# ir-reciever-test.net
KiCad netlist of a schematic drawn in EAGLE
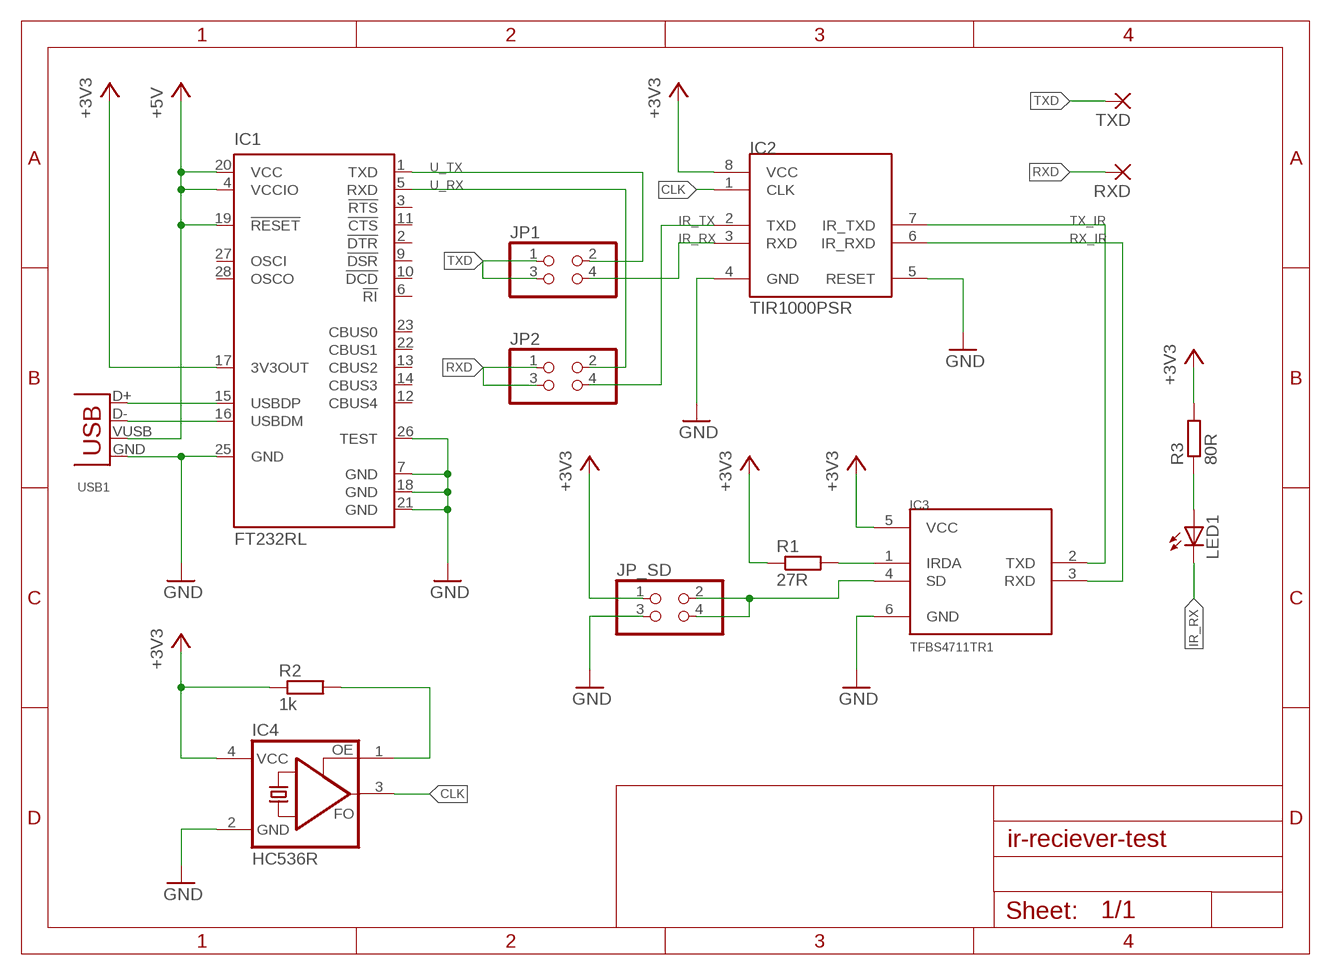
[diagram p0: schematic, sheet 1]

(export (version "E")
  (design (tool "Eeschema 10.0.6"))
  (components
    (comp (ref "IC1")
      (value "FT232RL")
      (footprint "eagle-import:SSOP28")
      (libsource (lib "eagle-import") (part "FT232RL"))
    )
    (comp (ref "IC2")
      (value "TIR1000PSR")
      (footprint "eagle-import:SO-08")
      (libsource (lib "eagle-import") (part "TIR1000PSR"))
    )
    (comp (ref "IC3")
      (value "TFBS4711TR1")
      (footprint "eagle-import:TFBS4711")
      (libsource (lib "eagle-import") (part "TFBS4711TR1"))
    )
    (comp (ref "IC4")
      (value "HC536R")
      (footprint "eagle-import:HC536")
      (libsource (lib "eagle-import") (part "HC536R"))
    )
    (comp (ref "JP1")
      (value "PINHD-2X02_2.54-SMD")
      (footprint "eagle-import:2X02SMD")
      (libsource (lib "eagle-import") (part "PINHD-2X02_2.54-SMD"))
    )
    (comp (ref "JP2")
      (value "PINHD-2X02_2.54-SMD")
      (footprint "eagle-import:2X02SMD")
      (libsource (lib "eagle-import") (part "PINHD-2X02_2.54-SMD"))
    )
    (comp (ref "JP_SD")
      (value "PINHD-2X02_2.54-SMD")
      (footprint "eagle-import:2X02SMD")
      (libsource (lib "eagle-import") (part "PINHD-2X02_2.54-SMD"))
    )
    (comp (ref "LED1")
      (value "LED3MM")
      (footprint "eagle-import:LED3MM")
      (libsource (lib "eagle-import") (part "LED3MM"))
    )
    (comp (ref "R1")
      (value "27R")
      (footprint "eagle-import:R1206")
      (libsource (lib "eagle-import") (part "R-EU_R1206"))
    )
    (comp (ref "R2")
      (value "1k")
      (footprint "eagle-import:R1206")
      (libsource (lib "eagle-import") (part "R-EU_R1206"))
    )
    (comp (ref "R3")
      (value "80R")
      (footprint "eagle-import:R1206")
      (libsource (lib "eagle-import") (part "R-EU_R1206"))
    )
    (comp (ref "RXD")
      (value "SMD5")
      (footprint "eagle-import:SMD2,54-5,08")
      (libsource (lib "eagle-import") (part "SMD5"))
    )
    (comp (ref "TXD")
      (value "SMD5")
      (footprint "eagle-import:SMD2,54-5,08")
      (libsource (lib "eagle-import") (part "SMD5"))
    )
    (comp (ref "USB1")
      (value "USB-B-S")
      (footprint "eagle-import:USB-B-SMT")
      (libsource (lib "eagle-import") (part "USB-B-S"))
    )
  )
  (nets
    (net (code "1") (name "+3V3") (class "Default")
      (node (ref "IC1") (pin "17") (pinfunction "3V3OUT_17") (pintype "output"))
      (node (ref "IC2") (pin "8") (pinfunction "VCC_8") (pintype "bidirectional"))
      (node (ref "IC3") (pin "5") (pinfunction "VCC_5") (pintype "power_in"))
      (node (ref "IC4") (pin "4") (pinfunction "VCC_4") (pintype "power_in"))
      (node (ref "JP_SD") (pin "1") (pinfunction "1_1") (pintype "passive"))
      (node (ref "R1") (pin "1") (pinfunction "1_1") (pintype "passive"))
      (node (ref "R2") (pin "1") (pinfunction "1_1") (pintype "passive"))
      (node (ref "R3") (pin "2") (pinfunction "2_2") (pintype "passive"))
    )
    (net (code "2") (name "+5V") (class "Default")
      (node (ref "IC1") (pin "19") (pinfunction "~{RESET}_19") (pintype "input"))
      (node (ref "IC1") (pin "20") (pinfunction "VCC_20") (pintype "power_in"))
      (node (ref "IC1") (pin "4") (pinfunction "VCCIO_4") (pintype "power_in"))
      (node (ref "USB1") (pin "VUSB") (pinfunction "VBUS_VUSB") (pintype "bidirectional"))
    )
    (net (code "3") (name "/IR_TX") (class "Default")
      (node (ref "IC2") (pin "2") (pinfunction "TXD_2") (pintype "bidirectional"))
      (node (ref "JP2") (pin "4") (pinfunction "4_4") (pintype "passive"))
    )
    (net (code "4") (name "/RX_IR") (class "Default")
      (node (ref "IC2") (pin "6") (pinfunction "IR_RXD_6") (pintype "bidirectional"))
      (node (ref "IC3") (pin "3") (pinfunction "RXD_3") (pintype "output"))
    )
    (net (code "5") (name "/TX_IR") (class "Default")
      (node (ref "IC2") (pin "7") (pinfunction "IR_TXD_7") (pintype "bidirectional"))
      (node (ref "IC3") (pin "2") (pinfunction "TXD_2") (pintype "input"))
    )
    (net (code "6") (name "/U_RX") (class "Default")
      (node (ref "IC1") (pin "5") (pinfunction "RXD_5") (pintype "input"))
      (node (ref "JP2") (pin "2") (pinfunction "2_2") (pintype "passive"))
    )
    (net (code "7") (name "/U_TX") (class "Default")
      (node (ref "IC1") (pin "1") (pinfunction "TXD_1") (pintype "output"))
      (node (ref "JP1") (pin "2") (pinfunction "2_2") (pintype "passive"))
    )
    (net (code "8") (name "CLK") (class "Default")
      (node (ref "IC2") (pin "1") (pinfunction "CLK_1") (pintype "bidirectional"))
      (node (ref "IC4") (pin "3") (pinfunction "FO_3") (pintype "output"))
    )
    (net (code "9") (name "GND") (class "Default")
      (node (ref "IC1") (pin "18") (pinfunction "GND_18") (pintype "power_in"))
      (node (ref "IC1") (pin "21") (pinfunction "GND_21") (pintype "power_in"))
      (node (ref "IC1") (pin "25") (pinfunction "GND_25") (pintype "power_in"))
      (node (ref "IC1") (pin "26") (pinfunction "TEST_26") (pintype "input"))
      (node (ref "IC1") (pin "7") (pinfunction "GND_7") (pintype "power_in"))
      (node (ref "IC2") (pin "4") (pinfunction "GND_4") (pintype "bidirectional"))
      (node (ref "IC2") (pin "5") (pinfunction "RESET_5") (pintype "bidirectional"))
      (node (ref "IC3") (pin "6") (pinfunction "GND_6") (pintype "bidirectional"))
      (node (ref "IC4") (pin "2") (pinfunction "GND_2") (pintype "power_in"))
      (node (ref "JP_SD") (pin "3") (pinfunction "3_3") (pintype "passive"))
      (node (ref "USB1") (pin "GND") (pinfunction "GND_GND") (pintype "bidirectional"))
    )
    (net (code "10") (name "IR_RX") (class "Default")
      (node (ref "IC2") (pin "3") (pinfunction "RXD_3") (pintype "bidirectional"))
      (node (ref "JP1") (pin "4") (pinfunction "4_4") (pintype "passive"))
      (node (ref "LED1") (pin "K") (pinfunction "C_K") (pintype "passive"))
    )
    (net (code "11") (name "Net-(IC1-USBDM)") (class "Default")
      (node (ref "IC1") (pin "16") (pinfunction "USBDM_16") (pintype "bidirectional"))
      (node (ref "USB1") (pin "D-") (pinfunction "D-_D-") (pintype "bidirectional"))
    )
    (net (code "12") (name "Net-(IC1-USBDP)") (class "Default")
      (node (ref "IC1") (pin "15") (pinfunction "USBDP_15") (pintype "bidirectional"))
      (node (ref "USB1") (pin "D+") (pinfunction "D+_D+") (pintype "bidirectional"))
    )
    (net (code "13") (name "Net-(IC3-IRDA)") (class "Default")
      (node (ref "IC3") (pin "1") (pinfunction "IRDA_1") (pintype "bidirectional"))
      (node (ref "R1") (pin "2") (pinfunction "2_2") (pintype "passive"))
    )
    (net (code "14") (name "Net-(IC3-SD)") (class "Default")
      (node (ref "IC3") (pin "4") (pinfunction "SD_4") (pintype "bidirectional"))
      (node (ref "JP_SD") (pin "2") (pinfunction "2_2") (pintype "passive"))
      (node (ref "JP_SD") (pin "4") (pinfunction "4_4") (pintype "passive"))
    )
    (net (code "15") (name "Net-(IC4-OE)") (class "Default")
      (node (ref "IC4") (pin "1") (pinfunction "OE_1") (pintype "input"))
      (node (ref "R2") (pin "2") (pinfunction "2_2") (pintype "passive"))
    )
    (net (code "16") (name "Net-(LED1-PadA)") (class "Default")
      (node (ref "LED1") (pin "A") (pinfunction "A_A") (pintype "passive"))
      (node (ref "R3") (pin "1") (pinfunction "1_1") (pintype "passive"))
    )
    (net (code "17") (name "RXD") (class "Default")
      (node (ref "JP2") (pin "1") (pinfunction "1_1") (pintype "passive"))
      (node (ref "JP2") (pin "3") (pinfunction "3_3") (pintype "passive"))
      (node (ref "RXD") (pin "1") (pinfunction "P_1") (pintype "passive"))
    )
    (net (code "18") (name "TXD") (class "Default")
      (node (ref "JP1") (pin "1") (pinfunction "1_1") (pintype "passive"))
      (node (ref "JP1") (pin "3") (pinfunction "3_3") (pintype "passive"))
      (node (ref "TXD") (pin "1") (pinfunction "P_1") (pintype "passive"))
    )
    (net (code "19") (name "unconnected-(IC1-CBUS0-Pad23)") (class "Default")
      (node (ref "IC1") (pin "23") (pinfunction "CBUS0_23") (pintype "bidirectional"))
    )
    (net (code "20") (name "unconnected-(IC1-CBUS1-Pad22)") (class "Default")
      (node (ref "IC1") (pin "22") (pinfunction "CBUS1_22") (pintype "bidirectional"))
    )
    (net (code "21") (name "unconnected-(IC1-CBUS2-Pad13)") (class "Default")
      (node (ref "IC1") (pin "13") (pinfunction "CBUS2_13") (pintype "bidirectional"))
    )
    (net (code "22") (name "unconnected-(IC1-CBUS3-Pad14)") (class "Default")
      (node (ref "IC1") (pin "14") (pinfunction "CBUS3_14") (pintype "bidirectional"))
    )
    (net (code "23") (name "unconnected-(IC1-CBUS4-Pad12)") (class "Default")
      (node (ref "IC1") (pin "12") (pinfunction "CBUS4_12") (pintype "bidirectional"))
    )
    (net (code "24") (name "unconnected-(IC1-OSCI-Pad27)") (class "Default")
      (node (ref "IC1") (pin "27") (pinfunction "OSCI_27") (pintype "input"))
    )
    (net (code "25") (name "unconnected-(IC1-OSCO-Pad28)") (class "Default")
      (node (ref "IC1") (pin "28") (pinfunction "OSCO_28") (pintype "output"))
    )
    (net (code "26") (name "unconnected-(IC1-~{CTS}-Pad11)") (class "Default")
      (node (ref "IC1") (pin "11") (pinfunction "~{CTS}_11") (pintype "input"))
    )
    (net (code "27") (name "unconnected-(IC1-~{DCD}-Pad10)") (class "Default")
      (node (ref "IC1") (pin "10") (pinfunction "~{DCD}_10") (pintype "input"))
    )
    (net (code "28") (name "unconnected-(IC1-~{DSR}-Pad9)") (class "Default")
      (node (ref "IC1") (pin "9") (pinfunction "~{DSR}_9") (pintype "input"))
    )
    (net (code "29") (name "unconnected-(IC1-~{DTR}-Pad2)") (class "Default")
      (node (ref "IC1") (pin "2") (pinfunction "~{DTR}_2") (pintype "output"))
    )
    (net (code "30") (name "unconnected-(IC1-~{RI}-Pad6)") (class "Default")
      (node (ref "IC1") (pin "6") (pinfunction "~{RI}_6") (pintype "input"))
    )
    (net (code "31") (name "unconnected-(IC1-~{RTS}-Pad3)") (class "Default")
      (node (ref "IC1") (pin "3") (pinfunction "~{RTS}_3") (pintype "output"))
    )
  )
)
